# Power_3V3.net
KiCad netlist of a schematic drawn in Altium Designer
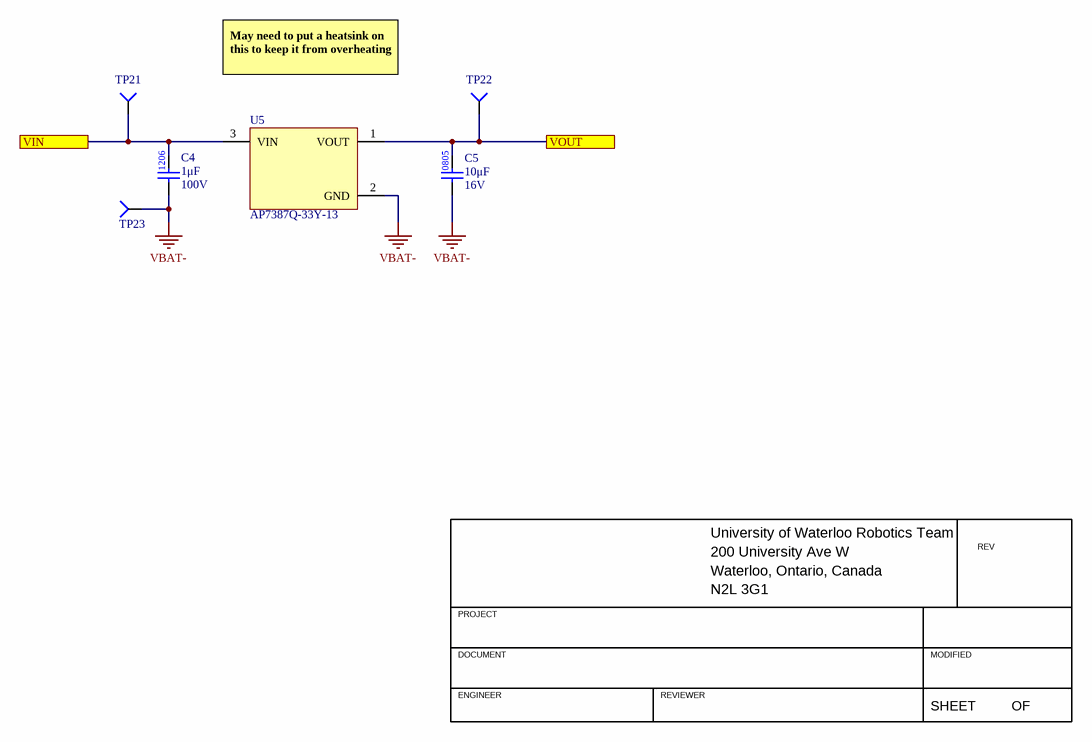
[diagram p0: Power_3V3.SchDoc]

(export (version "E")
  (design (tool "Eeschema 10.0.6"))
  (components
    (comp (ref "C4")
      (value "1μF")
      (footprint "CAPC3216X190X50NL20T25")
      (description "CAP CER 1UF 100V X7R 1206")
      (fields (field (name "VOLTAGE RATING") "100V") (field (name "Comment") "CAP_1uF_100V_1206"))
      (libsource (lib "Personal_Schematic_Library_2022") (part "CAP_1uF_100V_1206"))
    )
    (comp (ref "C5")
      (value "10μF")
      (footprint "CAP2012")
      (description "CAP CER 10UF 16V X5R 0805")
      (fields (field (name "VOLTAGE RATING") "16V") (field (name "Comment") "CAP_10uF_16V_0805"))
      (libsource (lib "Personal_Schematic_Library_2022") (part "CAP_10uF_16V_0805"))
    )
    (comp (ref "TP21")
      (value "TESTPOINT_SMD_LOOP")
      (footprint "S1751-46R")
      (description "TESTPOINT SMD LOOP")
      (libsource (lib "UWRT_Schematic_Library_2020") (part "TESTPOINT_SMD_LOOP"))
    )
    (comp (ref "TP22")
      (value "TESTPOINT_SMD_LOOP")
      (footprint "S1751-46R")
      (description "TESTPOINT SMD LOOP")
      (libsource (lib "UWRT_Schematic_Library_2020") (part "TESTPOINT_SMD_LOOP"))
    )
    (comp (ref "TP23")
      (value "TESTPOINT_SMD_LOOP")
      (footprint "S1751-46R")
      (description "TESTPOINT SMD LOOP")
      (libsource (lib "UWRT_Schematic_Library_2020") (part "TESTPOINT_SMD_LOOP"))
    )
    (comp (ref "U5")
      (value "LDO_3.3V_150mA_60VIN")
      (footprint "SOT89")
      (description "IC REG LINEAR 3.3V 150MA SOT89-3")
      (fields (field (name "MANUFACTURER PART NUMBER 1") "AP7387Q-33Y-13"))
      (libsource (lib "Personal_Schematic_Library_2022") (part "LDO_3.3V_150mA_60VIN"))
    )
  )
  (nets
    (net (code "1") (name "/VIN") (class "Default")
      (node (ref "C4") (pin "2") (pinfunction "2_2") (pintype "passive"))
      (node (ref "TP21") (pin "1") (pinfunction "=value_1") (pintype "passive"))
      (node (ref "U5") (pin "3") (pinfunction "VIN_3") (pintype "power_in"))
    )
    (net (code "2") (name "/VOUT") (class "Default")
      (node (ref "C5") (pin "2") (pinfunction "2_2") (pintype "passive"))
      (node (ref "TP22") (pin "1") (pinfunction "=value_1") (pintype "passive"))
      (node (ref "U5") (pin "1") (pinfunction "VOUT_1") (pintype "power_in"))
    )
    (net (code "3") (name "VBAT-") (class "Default")
      (node (ref "C4") (pin "1") (pinfunction "1_1") (pintype "passive"))
      (node (ref "C5") (pin "1") (pinfunction "1_1") (pintype "passive"))
      (node (ref "TP23") (pin "1") (pinfunction "=value_1") (pintype "passive"))
      (node (ref "U5") (pin "2") (pinfunction "GND_2") (pintype "power_in"))
    )
  )
)
